# CoderDojo-ESP-board.net
KiCad netlist of a schematic drawn in EAGLE
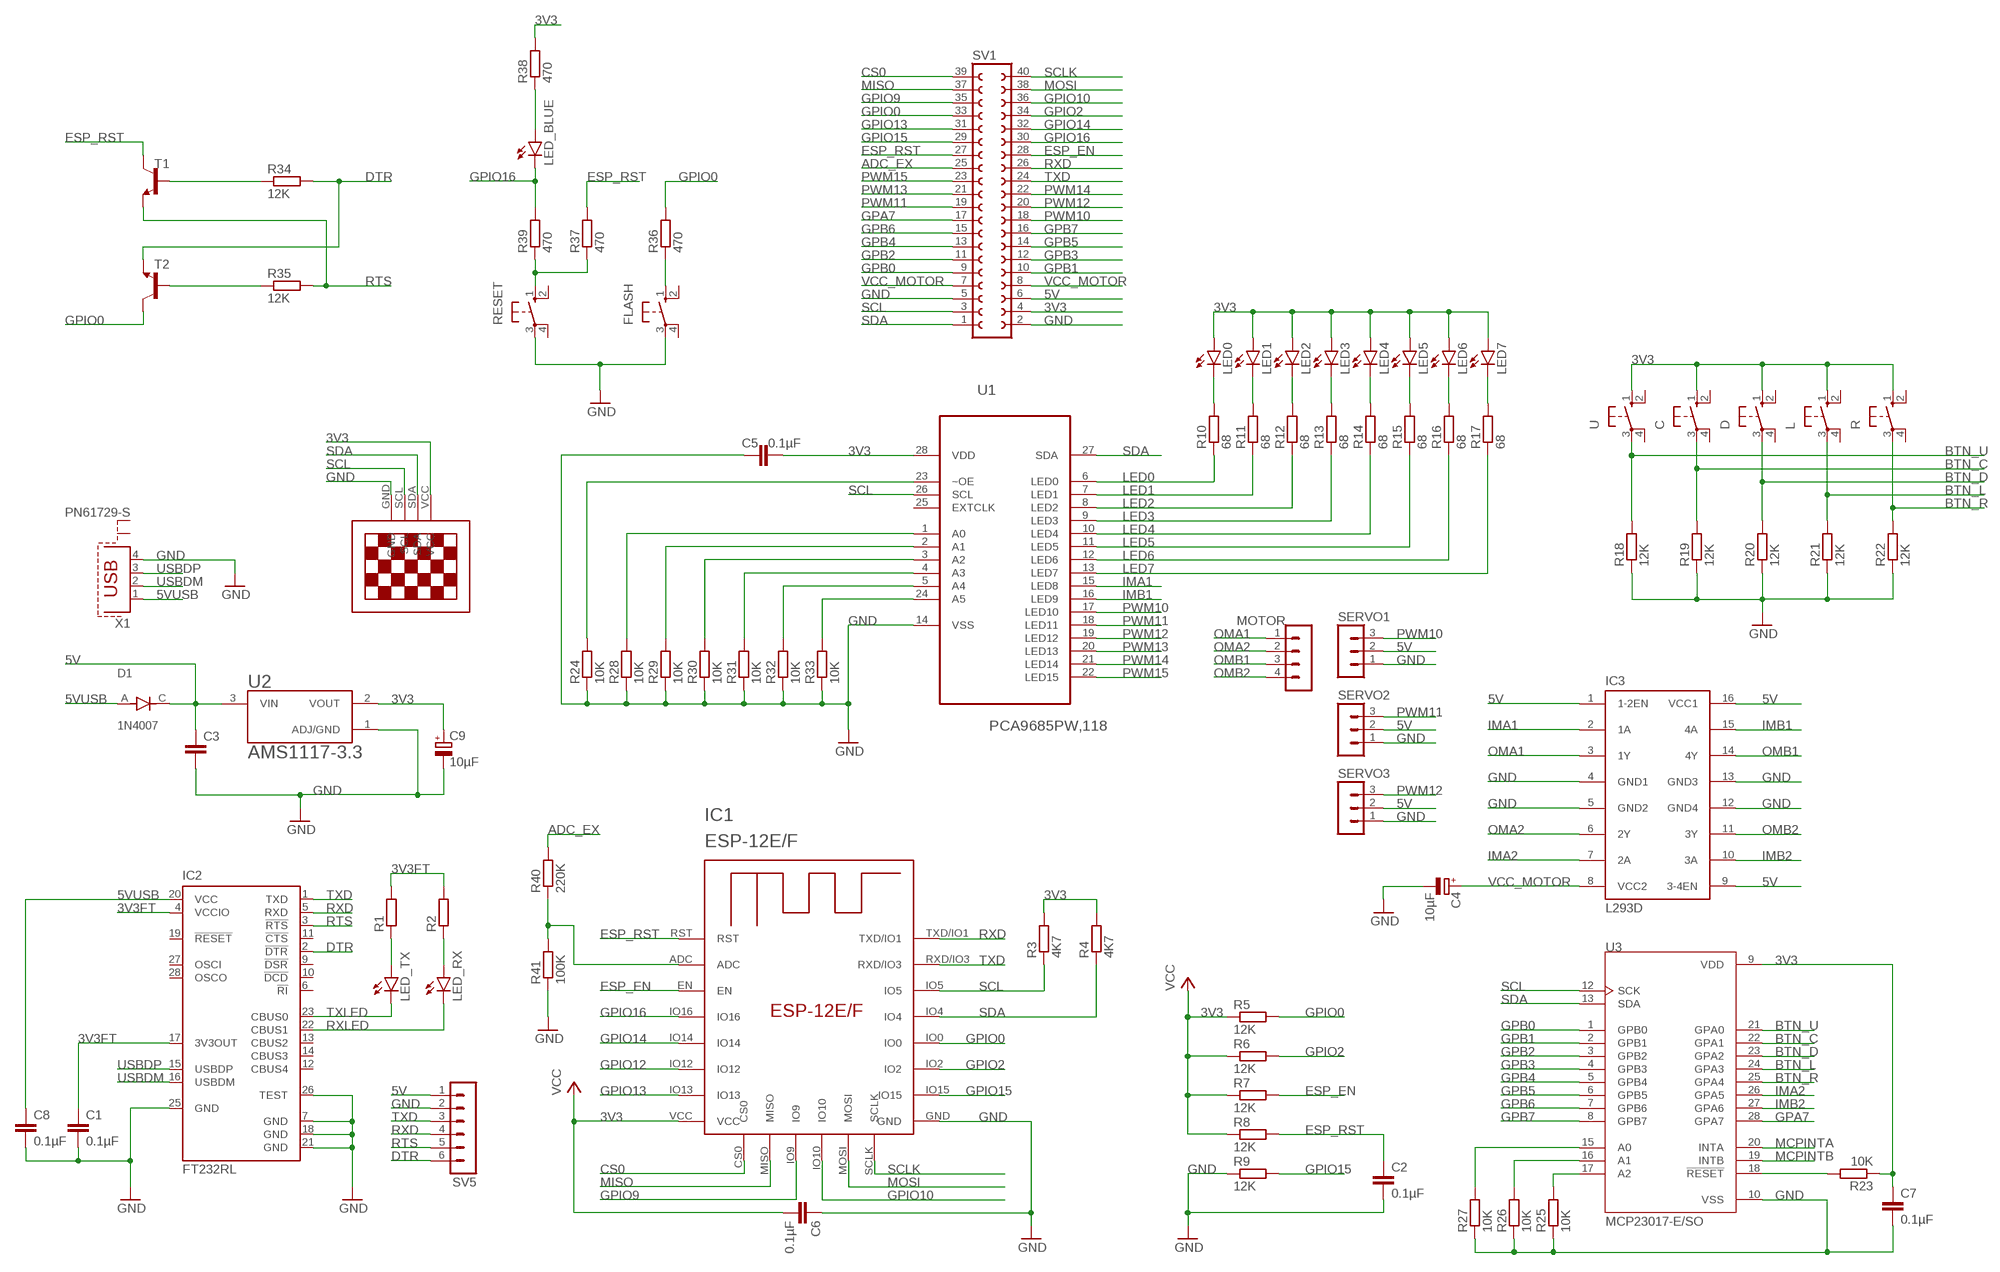
[diagram p0: schematic, sheet 1]

(export (version "E")
  (design (tool "Eeschema 10.0.6"))
  (components
    (comp (ref "C")
      (value "10-XX")
      (footprint "eagle-import:B3F-10XX")
      (fields (field (name "MPN") "B3F-1000"))
      (libsource (lib "eagle-import") (part "10-XX"))
    )
    (comp (ref "C1")
      (value "0.1µF")
      (footprint "eagle-import:C0805")
      (libsource (lib "eagle-import") (part "C-EUC0805"))
    )
    (comp (ref "C2")
      (value "0.1µF")
      (footprint "eagle-import:C0805")
      (libsource (lib "eagle-import") (part "C-EUC0805"))
    )
    (comp (ref "C3")
      (value "C-EUC0805")
      (footprint "eagle-import:C0805")
      (libsource (lib "eagle-import") (part "C-EUC0805"))
    )
    (comp (ref "C4")
      (value "10µF")
      (footprint "eagle-import:E2-5")
      (libsource (lib "eagle-import") (part "CPOL-EUE2-5"))
    )
    (comp (ref "C5")
      (value "0.1µF")
      (footprint "eagle-import:C0805")
      (libsource (lib "eagle-import") (part "C-EUC0805"))
    )
    (comp (ref "C6")
      (value "0.1µF")
      (footprint "eagle-import:C0805")
      (libsource (lib "eagle-import") (part "C-EUC0805"))
    )
    (comp (ref "C7")
      (value "0.1µF")
      (footprint "eagle-import:C0805")
      (libsource (lib "eagle-import") (part "C-EUC0805"))
    )
    (comp (ref "C8")
      (value "0.1µF")
      (footprint "eagle-import:C0805")
      (libsource (lib "eagle-import") (part "C-EUC0805"))
    )
    (comp (ref "C9")
      (value "10µF")
      (footprint "eagle-import:E2-5")
      (libsource (lib "eagle-import") (part "CPOL-EUE2-5"))
    )
    (comp (ref "D")
      (value "10-XX")
      (footprint "eagle-import:B3F-10XX")
      (fields (field (name "MPN") "B3F-1000"))
      (libsource (lib "eagle-import") (part "10-XX"))
    )
    (comp (ref "D1")
      (value "1N4007")
      (footprint "eagle-import:DIOAD1060W80L520D270")
      (fields (field (name "MF") "ON Semiconductor"))
      (libsource (lib "eagle-import") (part "1N4007"))
    )
    (comp (ref "FLASH")
      (value "10-XX")
      (footprint "eagle-import:B3F-10XX")
      (fields (field (name "MPN") "B3F-1000"))
      (libsource (lib "eagle-import") (part "10-XX"))
    )
    (comp (ref "IC1")
      (value "ESP-12E/F")
      (footprint "eagle-import:ESP-12E")
      (libsource (lib "eagle-import") (part "ESP-12E/F"))
    )
    (comp (ref "IC2")
      (value "FT232RL")
      (footprint "eagle-import:SSOP28")
      (libsource (lib "eagle-import") (part "FT232RL"))
    )
    (comp (ref "IC3")
      (value "L293D")
      (footprint "eagle-import:DIL16")
      (libsource (lib "eagle-import") (part "L293D"))
    )
    (comp (ref "L")
      (value "10-XX")
      (footprint "eagle-import:B3F-10XX")
      (fields (field (name "MPN") "B3F-1000"))
      (libsource (lib "eagle-import") (part "10-XX"))
    )
    (comp (ref "LED0")
      (value "LED3MM")
      (footprint "eagle-import:LED3MM")
      (libsource (lib "eagle-import") (part "LED3MM"))
    )
    (comp (ref "LED1")
      (value "LED3MM")
      (footprint "eagle-import:LED3MM")
      (libsource (lib "eagle-import") (part "LED3MM"))
    )
    (comp (ref "LED2")
      (value "LED3MM")
      (footprint "eagle-import:LED3MM")
      (libsource (lib "eagle-import") (part "LED3MM"))
    )
    (comp (ref "LED3")
      (value "LED3MM")
      (footprint "eagle-import:LED3MM")
      (libsource (lib "eagle-import") (part "LED3MM"))
    )
    (comp (ref "LED4")
      (value "LED3MM")
      (footprint "eagle-import:LED3MM")
      (libsource (lib "eagle-import") (part "LED3MM"))
    )
    (comp (ref "LED5")
      (value "LED3MM")
      (footprint "eagle-import:LED3MM")
      (libsource (lib "eagle-import") (part "LED3MM"))
    )
    (comp (ref "LED6")
      (value "LED3MM")
      (footprint "eagle-import:LED3MM")
      (libsource (lib "eagle-import") (part "LED3MM"))
    )
    (comp (ref "LED7")
      (value "LED3MM")
      (footprint "eagle-import:LED3MM")
      (libsource (lib "eagle-import") (part "LED3MM"))
    )
    (comp (ref "LED_BLUE")
      (value "LEDSML0805")
      (footprint "eagle-import:SML0805")
      (libsource (lib "eagle-import") (part "LEDSML0805"))
    )
    (comp (ref "LED_RX")
      (value "LEDSML0805")
      (footprint "eagle-import:SML0805")
      (libsource (lib "eagle-import") (part "LEDSML0805"))
    )
    (comp (ref "LED_TX")
      (value "LEDSML0805")
      (footprint "eagle-import:SML0805")
      (libsource (lib "eagle-import") (part "LEDSML0805"))
    )
    (comp (ref "MOTOR")
      (value "MA04-1")
      (footprint "eagle-import:MA04-1")
      (libsource (lib "eagle-import") (part "MA04-1"))
    )
    (comp (ref "R")
      (value "10-XX")
      (footprint "eagle-import:B3F-10XX")
      (fields (field (name "MPN") "B3F-1000"))
      (libsource (lib "eagle-import") (part "10-XX"))
    )
    (comp (ref "R1")
      (value "R-EU_R0805")
      (footprint "eagle-import:R0805")
      (libsource (lib "eagle-import") (part "R-EU_R0805"))
    )
    (comp (ref "R2")
      (value "R-EU_R0805")
      (footprint "eagle-import:R0805")
      (libsource (lib "eagle-import") (part "R-EU_R0805"))
    )
    (comp (ref "R3")
      (value "4K7")
      (footprint "eagle-import:R0805")
      (libsource (lib "eagle-import") (part "R-EU_R0805"))
    )
    (comp (ref "R4")
      (value "4K7")
      (footprint "eagle-import:R0805")
      (libsource (lib "eagle-import") (part "R-EU_R0805"))
    )
    (comp (ref "R5")
      (value "12K")
      (footprint "eagle-import:R0805")
      (libsource (lib "eagle-import") (part "R-EU_R0805"))
    )
    (comp (ref "R6")
      (value "12K")
      (footprint "eagle-import:R0805")
      (libsource (lib "eagle-import") (part "R-EU_R0805"))
    )
    (comp (ref "R7")
      (value "12K")
      (footprint "eagle-import:R0805")
      (libsource (lib "eagle-import") (part "R-EU_R0805"))
    )
    (comp (ref "R8")
      (value "12K")
      (footprint "eagle-import:R0805")
      (libsource (lib "eagle-import") (part "R-EU_R0805"))
    )
    (comp (ref "R9")
      (value "12K")
      (footprint "eagle-import:R0805")
      (libsource (lib "eagle-import") (part "R-EU_R0805"))
    )
    (comp (ref "R10")
      (value "68")
      (footprint "eagle-import:R0805")
      (libsource (lib "eagle-import") (part "R-EU_R0805"))
    )
    (comp (ref "R11")
      (value "68")
      (footprint "eagle-import:R0805")
      (libsource (lib "eagle-import") (part "R-EU_R0805"))
    )
    (comp (ref "R12")
      (value "68")
      (footprint "eagle-import:R0805")
      (libsource (lib "eagle-import") (part "R-EU_R0805"))
    )
    (comp (ref "R13")
      (value "68")
      (footprint "eagle-import:R0805")
      (libsource (lib "eagle-import") (part "R-EU_R0805"))
    )
    (comp (ref "R14")
      (value "68")
      (footprint "eagle-import:R0805")
      (libsource (lib "eagle-import") (part "R-EU_R0805"))
    )
    (comp (ref "R15")
      (value "68")
      (footprint "eagle-import:R0805")
      (libsource (lib "eagle-import") (part "R-EU_R0805"))
    )
    (comp (ref "R16")
      (value "68")
      (footprint "eagle-import:R0805")
      (libsource (lib "eagle-import") (part "R-EU_R0805"))
    )
    (comp (ref "R17")
      (value "68")
      (footprint "eagle-import:R0805")
      (libsource (lib "eagle-import") (part "R-EU_R0805"))
    )
    (comp (ref "R18")
      (value "12K")
      (footprint "eagle-import:R0805")
      (libsource (lib "eagle-import") (part "R-EU_R0805"))
    )
    (comp (ref "R19")
      (value "12K")
      (footprint "eagle-import:R0805")
      (libsource (lib "eagle-import") (part "R-EU_R0805"))
    )
    (comp (ref "R20")
      (value "12K")
      (footprint "eagle-import:R0805")
      (libsource (lib "eagle-import") (part "R-EU_R0805"))
    )
    (comp (ref "R21")
      (value "12K")
      (footprint "eagle-import:R0805")
      (libsource (lib "eagle-import") (part "R-EU_R0805"))
    )
    (comp (ref "R22")
      (value "12K")
      (footprint "eagle-import:R0805")
      (libsource (lib "eagle-import") (part "R-EU_R0805"))
    )
    (comp (ref "R23")
      (value "10K")
      (footprint "eagle-import:R0805")
      (libsource (lib "eagle-import") (part "R-EU_R0805"))
    )
    (comp (ref "R24")
      (value "10K")
      (footprint "eagle-import:R0805")
      (libsource (lib "eagle-import") (part "R-EU_R0805"))
    )
    (comp (ref "R25")
      (value "10K")
      (footprint "eagle-import:R0805")
      (libsource (lib "eagle-import") (part "R-EU_R0805"))
    )
    (comp (ref "R26")
      (value "10K")
      (footprint "eagle-import:R0805")
      (libsource (lib "eagle-import") (part "R-EU_R0805"))
    )
    (comp (ref "R27")
      (value "10K")
      (footprint "eagle-import:R0805")
      (libsource (lib "eagle-import") (part "R-EU_R0805"))
    )
    (comp (ref "R28")
      (value "10K")
      (footprint "eagle-import:R0805")
      (libsource (lib "eagle-import") (part "R-EU_R0805"))
    )
    (comp (ref "R29")
      (value "10K")
      (footprint "eagle-import:R0805")
      (libsource (lib "eagle-import") (part "R-EU_R0805"))
    )
    (comp (ref "R30")
      (value "10K")
      (footprint "eagle-import:R0805")
      (libsource (lib "eagle-import") (part "R-EU_R0805"))
    )
    (comp (ref "R31")
      (value "10K")
      (footprint "eagle-import:R0805")
      (libsource (lib "eagle-import") (part "R-EU_R0805"))
    )
    (comp (ref "R32")
      (value "10K")
      (footprint "eagle-import:R0805")
      (libsource (lib "eagle-import") (part "R-EU_R0805"))
    )
    (comp (ref "R33")
      (value "10K")
      (footprint "eagle-import:R0805")
      (libsource (lib "eagle-import") (part "R-EU_R0805"))
    )
    (comp (ref "R34")
      (value "12K")
      (footprint "eagle-import:R0805")
      (libsource (lib "eagle-import") (part "R-EU_R0805"))
    )
    (comp (ref "R35")
      (value "12K")
      (footprint "eagle-import:R0805")
      (libsource (lib "eagle-import") (part "R-EU_R0805"))
    )
    (comp (ref "R36")
      (value "470")
      (footprint "eagle-import:R0805")
      (libsource (lib "eagle-import") (part "R-EU_R0805"))
    )
    (comp (ref "R37")
      (value "470")
      (footprint "eagle-import:R0805")
      (libsource (lib "eagle-import") (part "R-EU_R0805"))
    )
    (comp (ref "R38")
      (value "470")
      (footprint "eagle-import:R0805")
      (libsource (lib "eagle-import") (part "R-EU_R0805"))
    )
    (comp (ref "R39")
      (value "470")
      (footprint "eagle-import:R0805")
      (libsource (lib "eagle-import") (part "R-EU_R0805"))
    )
    (comp (ref "R40")
      (value "220K")
      (footprint "eagle-import:R0805")
      (libsource (lib "eagle-import") (part "R-EU_R0805"))
    )
    (comp (ref "R41")
      (value "100K")
      (footprint "eagle-import:R0805")
      (libsource (lib "eagle-import") (part "R-EU_R0805"))
    )
    (comp (ref "RESET")
      (value "10-XX")
      (footprint "eagle-import:B3F-10XX")
      (fields (field (name "MPN") "B3F-1000"))
      (libsource (lib "eagle-import") (part "10-XX"))
    )
    (comp (ref "SERVO1")
      (value "MA03-1")
      (footprint "eagle-import:MA03-1")
      (libsource (lib "eagle-import") (part "MA03-1"))
    )
    (comp (ref "SERVO2")
      (value "MA03-1")
      (footprint "eagle-import:MA03-1")
      (libsource (lib "eagle-import") (part "MA03-1"))
    )
    (comp (ref "SERVO3")
      (value "MA03-1")
      (footprint "eagle-import:MA03-1")
      (libsource (lib "eagle-import") (part "MA03-1"))
    )
    (comp (ref "SV1")
      (value "FE20-2")
      (footprint "eagle-import:FE20-2")
      (libsource (lib "eagle-import") (part "FE20-2"))
    )
    (comp (ref "SV5")
      (value "MA06-1")
      (footprint "eagle-import:MA06-1")
      (libsource (lib "eagle-import") (part "MA06-1"))
    )
    (comp (ref "T1")
      (value "BC817-40-NPN-SOT23-BEC")
      (footprint "eagle-import:SOT23-BEC")
      (libsource (lib "eagle-import") (part "-NPN-SOT23-BECBC817-40"))
    )
    (comp (ref "T2")
      (value "BC817-40-NPN-SOT23-BEC")
      (footprint "eagle-import:SOT23-BEC")
      (libsource (lib "eagle-import") (part "-NPN-SOT23-BECBC817-40"))
    )
    (comp (ref "U")
      (value "10-XX")
      (footprint "eagle-import:B3F-10XX")
      (fields (field (name "MPN") "B3F-1000"))
      (libsource (lib "eagle-import") (part "10-XX"))
    )
    (comp (ref "U$1")
      (value "13\"OLED13\"OLED")
      (footprint "eagle-import:1.3_OLED")
      (libsource (lib "eagle-import") (part "13{dblquote}OLED13{dblquote}OLED"))
    )
    (comp (ref "U1")
      (value "PCA9685PW,118")
      (footprint "eagle-import:SOP65P640X110-28N")
      (fields (field (name "MF") "NXP USA"))
      (libsource (lib "eagle-import") (part "PCA9685PW,118"))
    )
    (comp (ref "U2")
      (value "AMS1117-3.3")
      (footprint "eagle-import:SOT229P700X180-4N")
      (fields (field (name "MF") "Advanced Monolithic Systems"))
      (libsource (lib "eagle-import") (part "AMS1117-3.3"))
    )
    (comp (ref "U3")
      (value "MCP23017-E/SO")
      (footprint "eagle-import:SOIC127P1030X265-28N")
      (fields (field (name "MF") "Microchip Technology"))
      (libsource (lib "eagle-import") (part "MCP23017-E/SO"))
    )
    (comp (ref "X1")
      (value "PN61729-S")
      (footprint "eagle-import:PN61729-S")
      (libsource (lib "eagle-import") (part "PN61729-S"))
    )
  )
  (nets
    (net (code "1") (name "3V3") (class "Default")
      (node (ref "C") (pin "1") (pinfunction "S_1") (pintype "passive"))
      (node (ref "C5") (pin "2") (pinfunction "2_2") (pintype "passive"))
      (node (ref "C6") (pin "2") (pinfunction "2_2") (pintype "passive"))
      (node (ref "C7") (pin "1") (pinfunction "1_1") (pintype "passive"))
      (node (ref "C9") (pin "+") (pinfunction "+_+") (pintype "passive"))
      (node (ref "D") (pin "1") (pinfunction "S_1") (pintype "passive"))
      (node (ref "IC1") (pin "VCC") (pinfunction "VCC_VCC") (pintype "power_in"))
      (node (ref "L") (pin "1") (pinfunction "S_1") (pintype "passive"))
      (node (ref "LED0") (pin "A") (pinfunction "A_A") (pintype "passive"))
      (node (ref "LED1") (pin "A") (pinfunction "A_A") (pintype "passive"))
      (node (ref "LED2") (pin "A") (pinfunction "A_A") (pintype "passive"))
      (node (ref "LED3") (pin "A") (pinfunction "A_A") (pintype "passive"))
      (node (ref "LED4") (pin "A") (pinfunction "A_A") (pintype "passive"))
      (node (ref "LED5") (pin "A") (pinfunction "A_A") (pintype "passive"))
      (node (ref "LED6") (pin "A") (pinfunction "A_A") (pintype "passive"))
      (node (ref "LED7") (pin "A") (pinfunction "A_A") (pintype "passive"))
      (node (ref "R") (pin "1") (pinfunction "S_1") (pintype "passive"))
      (node (ref "R23") (pin "1") (pinfunction "1_1") (pintype "passive"))
      (node (ref "R3") (pin "2") (pinfunction "2_2") (pintype "passive"))
      (node (ref "R38") (pin "2") (pinfunction "2_2") (pintype "passive"))
      (node (ref "R4") (pin "2") (pinfunction "2_2") (pintype "passive"))
      (node (ref "R5") (pin "1") (pinfunction "1_1") (pintype "passive"))
      (node (ref "R6") (pin "1") (pinfunction "1_1") (pintype "passive"))
      (node (ref "R7") (pin "1") (pinfunction "1_1") (pintype "passive"))
      (node (ref "R8") (pin "1") (pinfunction "1_1") (pintype "passive"))
      (node (ref "SV1") (pin "4") (pinfunction "4_4") (pintype "passive"))
      (node (ref "U") (pin "1") (pinfunction "S_1") (pintype "passive"))
      (node (ref "U$1") (pin "VCC") (pinfunction "VCC_VCC") (pintype "bidirectional"))
      (node (ref "U1") (pin "28") (pinfunction "VDD_28") (pintype "power_in"))
      (node (ref "U2") (pin "2") (pinfunction "VOUT_2") (pintype "output"))
      (node (ref "U3") (pin "9") (pinfunction "VDD_9") (pintype "power_in"))
    )
    (net (code "2") (name "3V3FT") (class "Default")
      (node (ref "C1") (pin "1") (pinfunction "1_1") (pintype "passive"))
      (node (ref "IC2") (pin "17") (pinfunction "3V3OUT_17") (pintype "output"))
      (node (ref "IC2") (pin "4") (pinfunction "VCCIO_4") (pintype "power_in"))
      (node (ref "R1") (pin "2") (pinfunction "2_2") (pintype "passive"))
      (node (ref "R2") (pin "2") (pinfunction "2_2") (pintype "passive"))
    )
    (net (code "3") (name "5V") (class "Default")
      (node (ref "C3") (pin "1") (pinfunction "1_1") (pintype "passive"))
      (node (ref "D1") (pin "C") (pinfunction "C_C") (pintype "passive"))
      (node (ref "IC3") (pin "1") (pinfunction "1-2EN_1") (pintype "input"))
      (node (ref "IC3") (pin "16") (pinfunction "VCC1_16") (pintype "power_in"))
      (node (ref "IC3") (pin "9") (pinfunction "3-4EN_9") (pintype "input"))
      (node (ref "SERVO1") (pin "2") (pinfunction "2_2") (pintype "passive"))
      (node (ref "SERVO2") (pin "2") (pinfunction "2_2") (pintype "passive"))
      (node (ref "SERVO3") (pin "2") (pinfunction "2_2") (pintype "passive"))
      (node (ref "SV1") (pin "6") (pinfunction "6_6") (pintype "passive"))
      (node (ref "SV5") (pin "1") (pinfunction "1_1") (pintype "passive"))
      (node (ref "U2") (pin "3") (pinfunction "VIN_3") (pintype "input"))
    )
    (net (code "4") (name "5VUSB") (class "Default")
      (node (ref "C8") (pin "1") (pinfunction "1_1") (pintype "passive"))
      (node (ref "D1") (pin "A") (pinfunction "A_A") (pintype "passive"))
      (node (ref "IC2") (pin "20") (pinfunction "VCC_20") (pintype "power_in"))
      (node (ref "X1") (pin "1") (pinfunction "1_1") (pintype "passive"))
    )
    (net (code "5") (name "ADC_EX") (class "Default")
      (node (ref "R40") (pin "2") (pinfunction "2_2") (pintype "passive"))
      (node (ref "SV1") (pin "25") (pinfunction "25_25") (pintype "passive"))
    )
    (net (code "6") (name "BTN_C") (class "Default")
      (node (ref "C") (pin "3") (pinfunction "P_3") (pintype "passive"))
      (node (ref "R19") (pin "2") (pinfunction "2_2") (pintype "passive"))
      (node (ref "U3") (pin "22") (pinfunction "GPA1_22") (pintype "bidirectional"))
    )
    (net (code "7") (name "BTN_D") (class "Default")
      (node (ref "D") (pin "3") (pinfunction "P_3") (pintype "passive"))
      (node (ref "R20") (pin "2") (pinfunction "2_2") (pintype "passive"))
      (node (ref "U3") (pin "23") (pinfunction "GPA2_23") (pintype "bidirectional"))
    )
    (net (code "8") (name "BTN_L") (class "Default")
      (node (ref "L") (pin "3") (pinfunction "P_3") (pintype "passive"))
      (node (ref "R21") (pin "2") (pinfunction "2_2") (pintype "passive"))
      (node (ref "U3") (pin "24") (pinfunction "GPA3_24") (pintype "bidirectional"))
    )
    (net (code "9") (name "BTN_R") (class "Default")
      (node (ref "R") (pin "3") (pinfunction "P_3") (pintype "passive"))
      (node (ref "R22") (pin "2") (pinfunction "2_2") (pintype "passive"))
      (node (ref "U3") (pin "25") (pinfunction "GPA4_25") (pintype "bidirectional"))
    )
    (net (code "10") (name "BTN_U") (class "Default")
      (node (ref "R18") (pin "2") (pinfunction "2_2") (pintype "passive"))
      (node (ref "U") (pin "3") (pinfunction "P_3") (pintype "passive"))
      (node (ref "U3") (pin "21") (pinfunction "GPA0_21") (pintype "bidirectional"))
    )
    (net (code "11") (name "CS0") (class "Default")
      (node (ref "IC1") (pin "CS0") (pinfunction "CS0_CS0") (pintype "bidirectional"))
      (node (ref "SV1") (pin "39") (pinfunction "39_39") (pintype "passive"))
    )
    (net (code "12") (name "DTR") (class "Default")
      (node (ref "IC2") (pin "2") (pinfunction "~{DTR}_2") (pintype "output"))
      (node (ref "R34") (pin "2") (pinfunction "2_2") (pintype "passive"))
      (node (ref "SV5") (pin "6") (pinfunction "6_6") (pintype "passive"))
      (node (ref "T2") (pin "E") (pinfunction "E_E") (pintype "passive"))
    )
    (net (code "13") (name "ESP_EN") (class "Default")
      (node (ref "IC1") (pin "EN") (pinfunction "EN_EN") (pintype "bidirectional"))
      (node (ref "R7") (pin "2") (pinfunction "2_2") (pintype "passive"))
      (node (ref "SV1") (pin "28") (pinfunction "28_28") (pintype "passive"))
    )
    (net (code "14") (name "ESP_RST") (class "Default")
      (node (ref "C2") (pin "1") (pinfunction "1_1") (pintype "passive"))
      (node (ref "IC1") (pin "RST") (pinfunction "RST_RST") (pintype "input"))
      (node (ref "R37") (pin "2") (pinfunction "2_2") (pintype "passive"))
      (node (ref "R8") (pin "2") (pinfunction "2_2") (pintype "passive"))
      (node (ref "SV1") (pin "27") (pinfunction "27_27") (pintype "passive"))
      (node (ref "T1") (pin "C") (pinfunction "C_C") (pintype "passive"))
    )
    (net (code "15") (name "GND") (class "Default")
      (node (ref "C1") (pin "2") (pinfunction "2_2") (pintype "passive"))
      (node (ref "C2") (pin "2") (pinfunction "2_2") (pintype "passive"))
      (node (ref "C3") (pin "2") (pinfunction "2_2") (pintype "passive"))
      (node (ref "C4") (pin "-") (pinfunction "-_-") (pintype "passive"))
      (node (ref "C5") (pin "1") (pinfunction "1_1") (pintype "passive"))
      (node (ref "C6") (pin "1") (pinfunction "1_1") (pintype "passive"))
      (node (ref "C7") (pin "2") (pinfunction "2_2") (pintype "passive"))
      (node (ref "C8") (pin "2") (pinfunction "2_2") (pintype "passive"))
      (node (ref "C9") (pin "-") (pinfunction "-_-") (pintype "passive"))
      (node (ref "FLASH") (pin "3") (pinfunction "P_3") (pintype "passive"))
      (node (ref "IC1") (pin "GND") (pinfunction "GND_GND") (pintype "power_in"))
      (node (ref "IC2") (pin "18") (pinfunction "GND_18") (pintype "power_in"))
      (node (ref "IC2") (pin "21") (pinfunction "GND_21") (pintype "power_in"))
      (node (ref "IC2") (pin "25") (pinfunction "GND_25") (pintype "power_in"))
      (node (ref "IC2") (pin "26") (pinfunction "TEST_26") (pintype "input"))
      (node (ref "IC2") (pin "7") (pinfunction "GND_7") (pintype "power_in"))
      (node (ref "IC3") (pin "12") (pinfunction "GND4_12") (pintype "power_in"))
      (node (ref "IC3") (pin "13") (pinfunction "GND3_13") (pintype "power_in"))
      (node (ref "IC3") (pin "4") (pinfunction "GND1_4") (pintype "power_in"))
      (node (ref "IC3") (pin "5") (pinfunction "GND2_5") (pintype "power_in"))
      (node (ref "R18") (pin "1") (pinfunction "1_1") (pintype "passive"))
      (node (ref "R19") (pin "1") (pinfunction "1_1") (pintype "passive"))
      (node (ref "R20") (pin "1") (pinfunction "1_1") (pintype "passive"))
      (node (ref "R21") (pin "1") (pinfunction "1_1") (pintype "passive"))
      (node (ref "R22") (pin "1") (pinfunction "1_1") (pintype "passive"))
      (node (ref "R24") (pin "1") (pinfunction "1_1") (pintype "passive"))
      (node (ref "R25") (pin "1") (pinfunction "1_1") (pintype "passive"))
      (node (ref "R26") (pin "1") (pinfunction "1_1") (pintype "passive"))
      (node (ref "R27") (pin "1") (pinfunction "1_1") (pintype "passive"))
      (node (ref "R28") (pin "1") (pinfunction "1_1") (pintype "passive"))
      (node (ref "R29") (pin "1") (pinfunction "1_1") (pintype "passive"))
      (node (ref "R30") (pin "1") (pinfunction "1_1") (pintype "passive"))
      (node (ref "R31") (pin "1") (pinfunction "1_1") (pintype "passive"))
      (node (ref "R32") (pin "1") (pinfunction "1_1") (pintype "passive"))
      (node (ref "R33") (pin "1") (pinfunction "1_1") (pintype "passive"))
      (node (ref "R41") (pin "1") (pinfunction "1_1") (pintype "passive"))
      (node (ref "R9") (pin "1") (pinfunction "1_1") (pintype "passive"))
      (node (ref "RESET") (pin "3") (pinfunction "P_3") (pintype "passive"))
      (node (ref "SERVO1") (pin "1") (pinfunction "1_1") (pintype "passive"))
      (node (ref "SERVO2") (pin "1") (pinfunction "1_1") (pintype "passive"))
      (node (ref "SERVO3") (pin "1") (pinfunction "1_1") (pintype "passive"))
      (node (ref "SV1") (pin "2") (pinfunction "2_2") (pintype "passive"))
      (node (ref "SV1") (pin "5") (pinfunction "5_5") (pintype "passive"))
      (node (ref "SV5") (pin "2") (pinfunction "2_2") (pintype "passive"))
      (node (ref "U$1") (pin "GND") (pinfunction "GND_GND") (pintype "bidirectional"))
      (node (ref "U1") (pin "14") (pinfunction "VSS_14") (pintype "passive"))
      (node (ref "U2") (pin "1") (pinfunction "ADJ/GND_1") (pintype "power_in"))
      (node (ref "U3") (pin "10") (pinfunction "VSS_10") (pintype "power_in"))
      (node (ref "X1") (pin "4") (pinfunction "4_4") (pintype "passive"))
    )
    (net (code "16") (name "GPA7") (class "Default")
      (node (ref "SV1") (pin "17") (pinfunction "17_17") (pintype "passive"))
      (node (ref "U3") (pin "28") (pinfunction "GPA7_28") (pintype "bidirectional"))
    )
    (net (code "17") (name "GPB0") (class "Default")
      (node (ref "SV1") (pin "9") (pinfunction "9_9") (pintype "passive"))
      (node (ref "U3") (pin "1") (pinfunction "GPB0_1") (pintype "bidirectional"))
    )
    (net (code "18") (name "GPB1") (class "Default")
      (node (ref "SV1") (pin "10") (pinfunction "10_10") (pintype "passive"))
      (node (ref "U3") (pin "2") (pinfunction "GPB1_2") (pintype "bidirectional"))
    )
    (net (code "19") (name "GPB2") (class "Default")
      (node (ref "SV1") (pin "11") (pinfunction "11_11") (pintype "passive"))
      (node (ref "U3") (pin "3") (pinfunction "GPB2_3") (pintype "bidirectional"))
    )
    (net (code "20") (name "GPB3") (class "Default")
      (node (ref "SV1") (pin "12") (pinfunction "12_12") (pintype "passive"))
      (node (ref "U3") (pin "4") (pinfunction "GPB3_4") (pintype "bidirectional"))
    )
    (net (code "21") (name "GPB4") (class "Default")
      (node (ref "SV1") (pin "13") (pinfunction "13_13") (pintype "passive"))
      (node (ref "U3") (pin "5") (pinfunction "GPB4_5") (pintype "bidirectional"))
    )
    (net (code "22") (name "GPB5") (class "Default")
      (node (ref "SV1") (pin "14") (pinfunction "14_14") (pintype "passive"))
      (node (ref "U3") (pin "6") (pinfunction "GPB5_6") (pintype "bidirectional"))
    )
    (net (code "23") (name "GPB6") (class "Default")
      (node (ref "SV1") (pin "15") (pinfunction "15_15") (pintype "passive"))
      (node (ref "U3") (pin "7") (pinfunction "GPB6_7") (pintype "bidirectional"))
    )
    (net (code "24") (name "GPB7") (class "Default")
      (node (ref "SV1") (pin "16") (pinfunction "16_16") (pintype "passive"))
      (node (ref "U3") (pin "8") (pinfunction "GPB7_8") (pintype "bidirectional"))
    )
    (net (code "25") (name "GPIO0") (class "Default")
      (node (ref "IC1") (pin "IO0") (pinfunction "IO0_IO0") (pintype "bidirectional"))
      (node (ref "R36") (pin "2") (pinfunction "2_2") (pintype "passive"))
      (node (ref "R5") (pin "2") (pinfunction "2_2") (pintype "passive"))
      (node (ref "SV1") (pin "33") (pinfunction "33_33") (pintype "passive"))
      (node (ref "T2") (pin "C") (pinfunction "C_C") (pintype "passive"))
    )
    (net (code "26") (name "GPIO2") (class "Default")
      (node (ref "IC1") (pin "IO2") (pinfunction "IO2_IO2") (pintype "bidirectional"))
      (node (ref "R6") (pin "2") (pinfunction "2_2") (pintype "passive"))
      (node (ref "SV1") (pin "34") (pinfunction "34_34") (pintype "passive"))
    )
    (net (code "27") (name "GPIO9") (class "Default")
      (node (ref "IC1") (pin "IO9") (pinfunction "IO9_IO9") (pintype "bidirectional"))
      (node (ref "SV1") (pin "35") (pinfunction "35_35") (pintype "passive"))
    )
    (net (code "28") (name "GPIO10") (class "Default")
      (node (ref "IC1") (pin "IO10") (pinfunction "IO10_IO10") (pintype "bidirectional"))
      (node (ref "SV1") (pin "36") (pinfunction "36_36") (pintype "passive"))
    )
    (net (code "29") (name "GPIO12") (class "Default")
      (node (ref "IC1") (pin "IO12") (pinfunction "IO12_IO12") (pintype "bidirectional"))
    )
    (net (code "30") (name "GPIO13") (class "Default")
      (node (ref "IC1") (pin "IO13") (pinfunction "IO13_IO13") (pintype "bidirectional"))
      (node (ref "SV1") (pin "31") (pinfunction "31_31") (pintype "passive"))
    )
    (net (code "31") (name "GPIO14") (class "Default")
      (node (ref "IC1") (pin "IO14") (pinfunction "IO14_IO14") (pintype "bidirectional"))
      (node (ref "SV1") (pin "32") (pinfunction "32_32") (pintype "passive"))
    )
    (net (code "32") (name "GPIO15") (class "Default")
      (node (ref "IC1") (pin "IO15") (pinfunction "IO15_IO15") (pintype "bidirectional"))
      (node (ref "R9") (pin "2") (pinfunction "2_2") (pintype "passive"))
      (node (ref "SV1") (pin "29") (pinfunction "29_29") (pintype "passive"))
    )
    (net (code "33") (name "GPIO16") (class "Default")
      (node (ref "IC1") (pin "IO16") (pinfunction "IO16_IO16") (pintype "bidirectional"))
      (node (ref "LED_BLUE") (pin "C") (pinfunction "C_C") (pintype "passive"))
      (node (ref "R39") (pin "2") (pinfunction "2_2") (pintype "passive"))
      (node (ref "SV1") (pin "30") (pinfunction "30_30") (pintype "passive"))
    )
    (net (code "34") (name "IMA1") (class "Default")
      (node (ref "IC3") (pin "2") (pinfunction "1A_2") (pintype "input"))
      (node (ref "U1") (pin "15") (pinfunction "LED8_15") (pintype "output"))
    )
    (net (code "35") (name "IMA2") (class "Default")
      (node (ref "IC3") (pin "7") (pinfunction "2A_7") (pintype "input"))
      (node (ref "U3") (pin "26") (pinfunction "GPA5_26") (pintype "bidirectional"))
    )
    (net (code "36") (name "IMB1") (class "Default")
      (node (ref "IC3") (pin "15") (pinfunction "4A_15") (pintype "input"))
      (node (ref "U1") (pin "16") (pinfunction "LED9_16") (pintype "output"))
    )
    (net (code "37") (name "IMB2") (class "Default")
      (node (ref "IC3") (pin "10") (pinfunction "3A_10") (pintype "input"))
      (node (ref "U3") (pin "27") (pinfunction "GPA6_27") (pintype "bidirectional"))
    )
    (net (code "38") (name "LED0") (class "Default")
      (node (ref "R10") (pin "1") (pinfunction "1_1") (pintype "passive"))
      (node (ref "U1") (pin "6") (pinfunction "LED0_6") (pintype "output"))
    )
    (net (code "39") (name "LED1") (class "Default")
      (node (ref "R11") (pin "1") (pinfunction "1_1") (pintype "passive"))
      (node (ref "U1") (pin "7") (pinfunction "LED1_7") (pintype "output"))
    )
    (net (code "40") (name "LED2") (class "Default")
      (node (ref "R12") (pin "1") (pinfunction "1_1") (pintype "passive"))
      (node (ref "U1") (pin "8") (pinfunction "LED2_8") (pintype "output"))
    )
    (net (code "41") (name "LED3") (class "Default")
      (node (ref "R13") (pin "1") (pinfunction "1_1") (pintype "passive"))
      (node (ref "U1") (pin "9") (pinfunction "LED3_9") (pintype "output"))
    )
    (net (code "42") (name "LED4") (class "Default")
      (node (ref "R14") (pin "1") (pinfunction "1_1") (pintype "passive"))
      (node (ref "U1") (pin "10") (pinfunction "LED4_10") (pintype "output"))
    )
    (net (code "43") (name "LED5") (class "Default")
      (node (ref "R15") (pin "1") (pinfunction "1_1") (pintype "passive"))
      (node (ref "U1") (pin "11") (pinfunction "LED5_11") (pintype "output"))
    )
    (net (code "44") (name "LED6") (class "Default")
      (node (ref "R16") (pin "1") (pinfunction "1_1") (pintype "passive"))
      (node (ref "U1") (pin "12") (pinfunction "LED6_12") (pintype "output"))
    )
    (net (code "45") (name "LED7") (class "Default")
      (node (ref "R17") (pin "1") (pinfunction "1_1") (pintype "passive"))
      (node (ref "U1") (pin "13") (pinfunction "LED7_13") (pintype "output"))
    )
    (net (code "46") (name "MCPINTA") (class "Default")
      (node (ref "U3") (pin "20") (pinfunction "INTA_20") (pintype "output"))
    )
    (net (code "47") (name "MCPINTB") (class "Default")
      (node (ref "U3") (pin "19") (pinfunction "INTB_19") (pintype "output"))
    )
    (net (code "48") (name "MISO") (class "Default")
      (node (ref "IC1") (pin "MISO") (pinfunction "MISO_MISO") (pintype "bidirectional"))
      (node (ref "SV1") (pin "37") (pinfunction "37_37") (pintype "passive"))
    )
    (net (code "49") (name "MOSI") (class "Default")
      (node (ref "IC1") (pin "MOSI") (pinfunction "MOSI_MOSI") (pintype "bidirectional"))
      (node (ref "SV1") (pin "38") (pinfunction "38_38") (pintype "passive"))
    )
    (net (code "50") (name "Net-(FLASH-S)") (class "Default")
      (node (ref "FLASH") (pin "1") (pinfunction "S_1") (pintype "passive"))
      (node (ref "R36") (pin "1") (pinfunction "1_1") (pintype "passive"))
    )
    (net (code "51") (name "Net-(IC1-PadADC)") (class "Default")
      (node (ref "IC1") (pin "ADC") (pinfunction "ADC_ADC") (pintype "bidirectional"))
      (node (ref "R40") (pin "1") (pinfunction "1_1") (pintype "passive"))
      (node (ref "R41") (pin "2") (pinfunction "2_2") (pintype "passive"))
    )
    (net (code "52") (name "Net-(LED0-C)") (class "Default")
      (node (ref "LED0") (pin "K") (pinfunction "C_K") (pintype "passive"))
      (node (ref "R10") (pin "2") (pinfunction "2_2") (pintype "passive"))
    )
    (net (code "53") (name "Net-(LED1-C)") (class "Default")
      (node (ref "LED1") (pin "K") (pinfunction "C_K") (pintype "passive"))
      (node (ref "R11") (pin "2") (pinfunction "2_2") (pintype "passive"))
    )
    (net (code "54") (name "Net-(LED2-C)") (class "Default")
      (node (ref "LED2") (pin "K") (pinfunction "C_K") (pintype "passive"))
      (node (ref "R12") (pin "2") (pinfunction "2_2") (pintype "passive"))
    )
    (net (code "55") (name "Net-(LED3-C)") (class "Default")
      (node (ref "LED3") (pin "K") (pinfunction "C_K") (pintype "passive"))
      (node (ref "R13") (pin "2") (pinfunction "2_2") (pintype "passive"))
    )
    (net (code "56") (name "Net-(LED4-C)") (class "Default")
      (node (ref "LED4") (pin "K") (pinfunction "C_K") (pintype "passive"))
      (node (ref "R14") (pin "2") (pinfunction "2_2") (pintype "passive"))
    )
    (net (code "57") (name "Net-(LED5-C)") (class "Default")
      (node (ref "LED5") (pin "K") (pinfunction "C_K") (pintype "passive"))
      (node (ref "R15") (pin "2") (pinfunction "2_2") (pintype "passive"))
    )
    (net (code "58") (name "Net-(LED6-C)") (class "Default")
      (node (ref "LED6") (pin "K") (pinfunction "C_K") (pintype "passive"))
      (node (ref "R16") (pin "2") (pinfunction "2_2") (pintype "passive"))
    )
    (net (code "59") (name "Net-(LED7-C)") (class "Default")
      (node (ref "LED7") (pin "K") (pinfunction "C_K") (pintype "passive"))
      (node (ref "R17") (pin "2") (pinfunction "2_2") (pintype "passive"))
    )
    (net (code "60") (name "Net-(LED_BLUE-PadA)") (class "Default")
      (node (ref "LED_BLUE") (pin "A") (pinfunction "A_A") (pintype "passive"))
      (node (ref "R38") (pin "1") (pinfunction "1_1") (pintype "passive"))
    )
    (net (code "61") (name "Net-(LED_RX-PadA)") (class "Default")
      (node (ref "LED_RX") (pin "A") (pinfunction "A_A") (pintype "passive"))
      (node (ref "R2") (pin "1") (pinfunction "1_1") (pintype "passive"))
    )
    (net (code "62") (name "Net-(LED_TX-PadA)") (class "Default")
      (node (ref "LED_TX") (pin "A") (pinfunction "A_A") (pintype "passive"))
      (node (ref "R1") (pin "1") (pinfunction "1_1") (pintype "passive"))
    )
    (net (code "63") (name "Net-(R34-Pad1)") (class "Default")
      (node (ref "R34") (pin "1") (pinfunction "1_1") (pintype "passive"))
      (node (ref "T1") (pin "B") (pinfunction "B_B") (pintype "passive"))
    )
    (net (code "64") (name "Net-(R35-Pad1)") (class "Default")
      (node (ref "R35") (pin "1") (pinfunction "1_1") (pintype "passive"))
      (node (ref "T2") (pin "B") (pinfunction "B_B") (pintype "passive"))
    )
    (net (code "65") (name "Net-(RESET-S)") (class "Default")
      (node (ref "R37") (pin "1") (pinfunction "1_1") (pintype "passive"))
      (node (ref "R39") (pin "1") (pinfunction "1_1") (pintype "passive"))
      (node (ref "RESET") (pin "1") (pinfunction "S_1") (pintype "passive"))
    )
    (net (code "66") (name "Net-(U1-A0)") (class "Default")
      (node (ref "R28") (pin "2") (pinfunction "2_2") (pintype "passive"))
      (node (ref "U1") (pin "1") (pinfunction "A0_1") (pintype "input"))
    )
    (net (code "67") (name "Net-(U1-A1)") (class "Default")
      (node (ref "R29") (pin "2") (pinfunction "2_2") (pintype "passive"))
      (node (ref "U1") (pin "2") (pinfunction "A1_2") (pintype "input"))
    )
    (net (code "68") (name "Net-(U1-A2)") (class "Default")
      (node (ref "R30") (pin "2") (pinfunction "2_2") (pintype "passive"))
      (node (ref "U1") (pin "3") (pinfunction "A2_3") (pintype "input"))
    )
    (net (code "69") (name "Net-(U1-A3)") (class "Default")
      (node (ref "R31") (pin "2") (pinfunction "2_2") (pintype "passive"))
      (node (ref "U1") (pin "4") (pinfunction "A3_4") (pintype "input"))
    )
    (net (code "70") (name "Net-(U1-A4)") (class "Default")
      (node (ref "R32") (pin "2") (pinfunction "2_2") (pintype "passive"))
      (node (ref "U1") (pin "5") (pinfunction "A4_5") (pintype "input"))
    )
    (net (code "71") (name "Net-(U1-A5)") (class "Default")
      (node (ref "R33") (pin "2") (pinfunction "2_2") (pintype "passive"))
      (node (ref "U1") (pin "24") (pinfunction "A5_24") (pintype "input"))
    )
    (net (code "72") (name "Net-(U1-~{OE})") (class "Default")
      (node (ref "R24") (pin "2") (pinfunction "2_2") (pintype "passive"))
      (node (ref "U1") (pin "23") (pinfunction "~{OE}_23") (pintype "input"))
    )
    (net (code "73") (name "Net-(U3-A0)") (class "Default")
      (node (ref "R27") (pin "2") (pinfunction "2_2") (pintype "passive"))
      (node (ref "U3") (pin "15") (pinfunction "A0_15") (pintype "input"))
    )
    (net (code "74") (name "Net-(U3-A1)") (class "Default")
      (node (ref "R26") (pin "2") (pinfunction "2_2") (pintype "passive"))
      (node (ref "U3") (pin "16") (pinfunction "A1_16") (pintype "input"))
    )
    (net (code "75") (name "Net-(U3-A2)") (class "Default")
      (node (ref "R25") (pin "2") (pinfunction "2_2") (pintype "passive"))
      (node (ref "U3") (pin "17") (pinfunction "A2_17") (pintype "input"))
    )
    (net (code "76") (name "Net-(U3-~{RESET})") (class "Default")
      (node (ref "R23") (pin "2") (pinfunction "2_2") (pintype "passive"))
      (node (ref "U3") (pin "18") (pinfunction "~{RESET}_18") (pintype "output"))
    )
    (net (code "77") (name "OMA1") (class "Default")
      (node (ref "IC3") (pin "3") (pinfunction "1Y_3") (pintype "output"))
      (node (ref "MOTOR") (pin "1") (pinfunction "1_1") (pintype "passive"))
    )
    (net (code "78") (name "OMA2") (class "Default")
      (node (ref "IC3") (pin "6") (pinfunction "2Y_6") (pintype "output"))
      (node (ref "MOTOR") (pin "2") (pinfunction "2_2") (pintype "passive"))
    )
    (net (code "79") (name "OMB1") (class "Default")
      (node (ref "IC3") (pin "14") (pinfunction "4Y_14") (pintype "output"))
      (node (ref "MOTOR") (pin "3") (pinfunction "3_3") (pintype "passive"))
    )
    (net (code "80") (name "OMB2") (class "Default")
      (node (ref "IC3") (pin "11") (pinfunction "3Y_11") (pintype "output"))
      (node (ref "MOTOR") (pin "4") (pinfunction "4_4") (pintype "passive"))
    )
    (net (code "81") (name "PWM10") (class "Default")
      (node (ref "SERVO1") (pin "3") (pinfunction "3_3") (pintype "passive"))
      (node (ref "SV1") (pin "18") (pinfunction "18_18") (pintype "passive"))
      (node (ref "U1") (pin "17") (pinfunction "LED10_17") (pintype "output"))
    )
    (net (code "82") (name "PWM11") (class "Default")
      (node (ref "SERVO2") (pin "3") (pinfunction "3_3") (pintype "passive"))
      (node (ref "SV1") (pin "19") (pinfunction "19_19") (pintype "passive"))
      (node (ref "U1") (pin "18") (pinfunction "LED11_18") (pintype "output"))
    )
    (net (code "83") (name "PWM12") (class "Default")
      (node (ref "SERVO3") (pin "3") (pinfunction "3_3") (pintype "passive"))
      (node (ref "SV1") (pin "20") (pinfunction "20_20") (pintype "passive"))
      (node (ref "U1") (pin "19") (pinfunction "LED12_19") (pintype "output"))
    )
    (net (code "84") (name "PWM13") (class "Default")
      (node (ref "SV1") (pin "21") (pinfunction "21_21") (pintype "passive"))
      (node (ref "U1") (pin "20") (pinfunction "LED13_20") (pintype "output"))
    )
    (net (code "85") (name "PWM14") (class "Default")
      (node (ref "SV1") (pin "22") (pinfunction "22_22") (pintype "passive"))
      (node (ref "U1") (pin "21") (pinfunction "LED14_21") (pintype "output"))
    )
    (net (code "86") (name "PWM15") (class "Default")
      (node (ref "SV1") (pin "23") (pinfunction "23_23") (pintype "passive"))
      (node (ref "U1") (pin "22") (pinfunction "LED15_22") (pintype "output"))
    )
    (net (code "87") (name "RTS") (class "Default")
      (node (ref "IC2") (pin "3") (pinfunction "~{RTS}_3") (pintype "output"))
      (node (ref "R35") (pin "2") (pinfunction "2_2") (pintype "passive"))
      (node (ref "SV5") (pin "5") (pinfunction "5_5") (pintype "passive"))
      (node (ref "T1") (pin "E") (pinfunction "E_E") (pintype "passive"))
    )
    (net (code "88") (name "RXD") (class "Default")
      (node (ref "IC1") (pin "TXD/IO1") (pinfunction "TXD/IO1_TXD/IO1") (pintype "bidirectional"))
      (node (ref "IC2") (pin "5") (pinfunction "RXD_5") (pintype "input"))
      (node (ref "SV1") (pin "26") (pinfunction "26_26") (pintype "passive"))
      (node (ref "SV5") (pin "4") (pinfunction "4_4") (pintype "passive"))
    )
    (net (code "89") (name "RXLED") (class "Default")
      (node (ref "IC2") (pin "22") (pinfunction "CBUS1_22") (pintype "bidirectional"))
      (node (ref "LED_RX") (pin "C") (pinfunction "C_C") (pintype "passive"))
    )
    (net (code "90") (name "SCL") (class "Default")
      (node (ref "IC1") (pin "IO5") (pinfunction "IO5_IO5") (pintype "bidirectional"))
      (node (ref "R3") (pin "1") (pinfunction "1_1") (pintype "passive"))
      (node (ref "SV1") (pin "3") (pinfunction "3_3") (pintype "passive"))
      (node (ref "U$1") (pin "SCL") (pinfunction "SCL_SCL") (pintype "bidirectional"))
      (node (ref "U1") (pin "26") (pinfunction "SCL_26") (pintype "input"))
      (node (ref "U3") (pin "12") (pinfunction "SCK_12") (pintype "input"))
    )
    (net (code "91") (name "SCLK") (class "Default")
      (node (ref "IC1") (pin "SCLK") (pinfunction "SCLK_SCLK") (pintype "bidirectional"))
      (node (ref "SV1") (pin "40") (pinfunction "40_40") (pintype "passive"))
    )
    (net (code "92") (name "SDA") (class "Default")
      (node (ref "IC1") (pin "IO4") (pinfunction "IO4_IO4") (pintype "bidirectional"))
      (node (ref "R4") (pin "1") (pinfunction "1_1") (pintype "passive"))
      (node (ref "SV1") (pin "1") (pinfunction "1_1") (pintype "passive"))
      (node (ref "U$1") (pin "SDA") (pinfunction "SDA_SDA") (pintype "bidirectional"))
      (node (ref "U1") (pin "27") (pinfunction "SDA_27") (pintype "bidirectional"))
      (node (ref "U3") (pin "13") (pinfunction "SDA_13") (pintype "bidirectional"))
    )
    (net (code "93") (name "TXD") (class "Default")
      (node (ref "IC1") (pin "RXD/IO3") (pinfunction "RXD/IO3_RXD/IO3") (pintype "bidirectional"))
      (node (ref "IC2") (pin "1") (pinfunction "TXD_1") (pintype "output"))
      (node (ref "SV1") (pin "24") (pinfunction "24_24") (pintype "passive"))
      (node (ref "SV5") (pin "3") (pinfunction "3_3") (pintype "passive"))
    )
    (net (code "94") (name "TXLED") (class "Default")
      (node (ref "IC2") (pin "23") (pinfunction "CBUS0_23") (pintype "bidirectional"))
      (node (ref "LED_TX") (pin "C") (pinfunction "C_C") (pintype "passive"))
    )
    (net (code "95") (name "USBDM") (class "Default")
      (node (ref "IC2") (pin "16") (pinfunction "USBDM_16") (pintype "bidirectional"))
      (node (ref "X1") (pin "2") (pinfunction "2_2") (pintype "passive"))
    )
    (net (code "96") (name "USBDP") (class "Default")
      (node (ref "IC2") (pin "15") (pinfunction "USBDP_15") (pintype "bidirectional"))
      (node (ref "X1") (pin "3") (pinfunction "3_3") (pintype "passive"))
    )
    (net (code "97") (name "VCC_MOTOR") (class "Default")
      (node (ref "C4") (pin "+") (pinfunction "+_+") (pintype "passive"))
      (node (ref "IC3") (pin "8") (pinfunction "VCC2_8") (pintype "power_in"))
      (node (ref "SV1") (pin "7") (pinfunction "7_7") (pintype "passive"))
      (node (ref "SV1") (pin "8") (pinfunction "8_8") (pintype "passive"))
    )
    (net (code "98") (name "unconnected-(C-P1-Pad4)") (class "Default")
      (node (ref "C") (pin "4") (pinfunction "P1_4") (pintype "passive"))
    )
    (net (code "99") (name "unconnected-(C-S1-Pad2)") (class "Default")
      (node (ref "C") (pin "2") (pinfunction "S1_2") (pintype "passive"))
    )
    (net (code "100") (name "unconnected-(D-P1-Pad4)") (class "Default")
      (node (ref "D") (pin "4") (pinfunction "P1_4") (pintype "passive"))
    )
    (net (code "101") (name "unconnected-(D-S1-Pad2)") (class "Default")
      (node (ref "D") (pin "2") (pinfunction "S1_2") (pintype "passive"))
    )
    (net (code "102") (name "unconnected-(FLASH-P1-Pad4)") (class "Default")
      (node (ref "FLASH") (pin "4") (pinfunction "P1_4") (pintype "passive"))
    )
    (net (code "103") (name "unconnected-(FLASH-S1-Pad2)") (class "Default")
      (node (ref "FLASH") (pin "2") (pinfunction "S1_2") (pintype "passive"))
    )
    (net (code "104") (name "unconnected-(IC2-CBUS2-Pad13)") (class "Default")
      (node (ref "IC2") (pin "13") (pinfunction "CBUS2_13") (pintype "bidirectional"))
    )
    (net (code "105") (name "unconnected-(IC2-CBUS3-Pad14)") (class "Default")
      (node (ref "IC2") (pin "14") (pinfunction "CBUS3_14") (pintype "bidirectional"))
    )
    (net (code "106") (name "unconnected-(IC2-CBUS4-Pad12)") (class "Default")
      (node (ref "IC2") (pin "12") (pinfunction "CBUS4_12") (pintype "bidirectional"))
    )
    (net (code "107") (name "unconnected-(IC2-OSCI-Pad27)") (class "Default")
      (node (ref "IC2") (pin "27") (pinfunction "OSCI_27") (pintype "input"))
    )
    (net (code "108") (name "unconnected-(IC2-OSCO-Pad28)") (class "Default")
      (node (ref "IC2") (pin "28") (pinfunction "OSCO_28") (pintype "output"))
    )
    (net (code "109") (name "unconnected-(IC2-~{CTS}-Pad11)") (class "Default")
      (node (ref "IC2") (pin "11") (pinfunction "~{CTS}_11") (pintype "input"))
    )
    (net (code "110") (name "unconnected-(IC2-~{DCD}-Pad10)") (class "Default")
      (node (ref "IC2") (pin "10") (pinfunction "~{DCD}_10") (pintype "input"))
    )
    (net (code "111") (name "unconnected-(IC2-~{DSR}-Pad9)") (class "Default")
      (node (ref "IC2") (pin "9") (pinfunction "~{DSR}_9") (pintype "input"))
    )
    (net (code "112") (name "unconnected-(IC2-~{RESET}-Pad19)") (class "Default")
      (node (ref "IC2") (pin "19") (pinfunction "~{RESET}_19") (pintype "input"))
    )
    (net (code "113") (name "unconnected-(IC2-~{RI}-Pad6)") (class "Default")
      (node (ref "IC2") (pin "6") (pinfunction "~{RI}_6") (pintype "input"))
    )
    (net (code "114") (name "unconnected-(L-P1-Pad4)") (class "Default")
      (node (ref "L") (pin "4") (pinfunction "P1_4") (pintype "passive"))
    )
    (net (code "115") (name "unconnected-(L-S1-Pad2)") (class "Default")
      (node (ref "L") (pin "2") (pinfunction "S1_2") (pintype "passive"))
    )
    (net (code "116") (name "unconnected-(R-P1-Pad4)") (class "Default")
      (node (ref "R") (pin "4") (pinfunction "P1_4") (pintype "passive"))
    )
    (net (code "117") (name "unconnected-(R-S1-Pad2)") (class "Default")
      (node (ref "R") (pin "2") (pinfunction "S1_2") (pintype "passive"))
    )
    (net (code "118") (name "unconnected-(RESET-P1-Pad4)") (class "Default")
      (node (ref "RESET") (pin "4") (pinfunction "P1_4") (pintype "passive"))
    )
    (net (code "119") (name "unconnected-(RESET-S1-Pad2)") (class "Default")
      (node (ref "RESET") (pin "2") (pinfunction "S1_2") (pintype "passive"))
    )
    (net (code "120") (name "unconnected-(U-P1-Pad4)") (class "Default")
      (node (ref "U") (pin "4") (pinfunction "P1_4") (pintype "passive"))
    )
    (net (code "121") (name "unconnected-(U-S1-Pad2)") (class "Default")
      (node (ref "U") (pin "2") (pinfunction "S1_2") (pintype "passive"))
    )
    (net (code "122") (name "unconnected-(U1-EXTCLK-Pad25)") (class "Default")
      (node (ref "U1") (pin "25") (pinfunction "EXTCLK_25") (pintype "input"))
    )
    (net (code "123") (name "unconnected-(X1-PadS1)") (class "Default")
      (node (ref "X1") (pin "S1") (pinfunction "S1_S1") (pintype "passive"))
    )
    (net (code "124") (name "unconnected-(X1-PadS2)") (class "Default")
      (node (ref "X1") (pin "S2") (pinfunction "S2_S2") (pintype "passive"))
    )
  )
)
